# controller_rev4_1.net
KiCad netlist of a schematic drawn in EAGLE
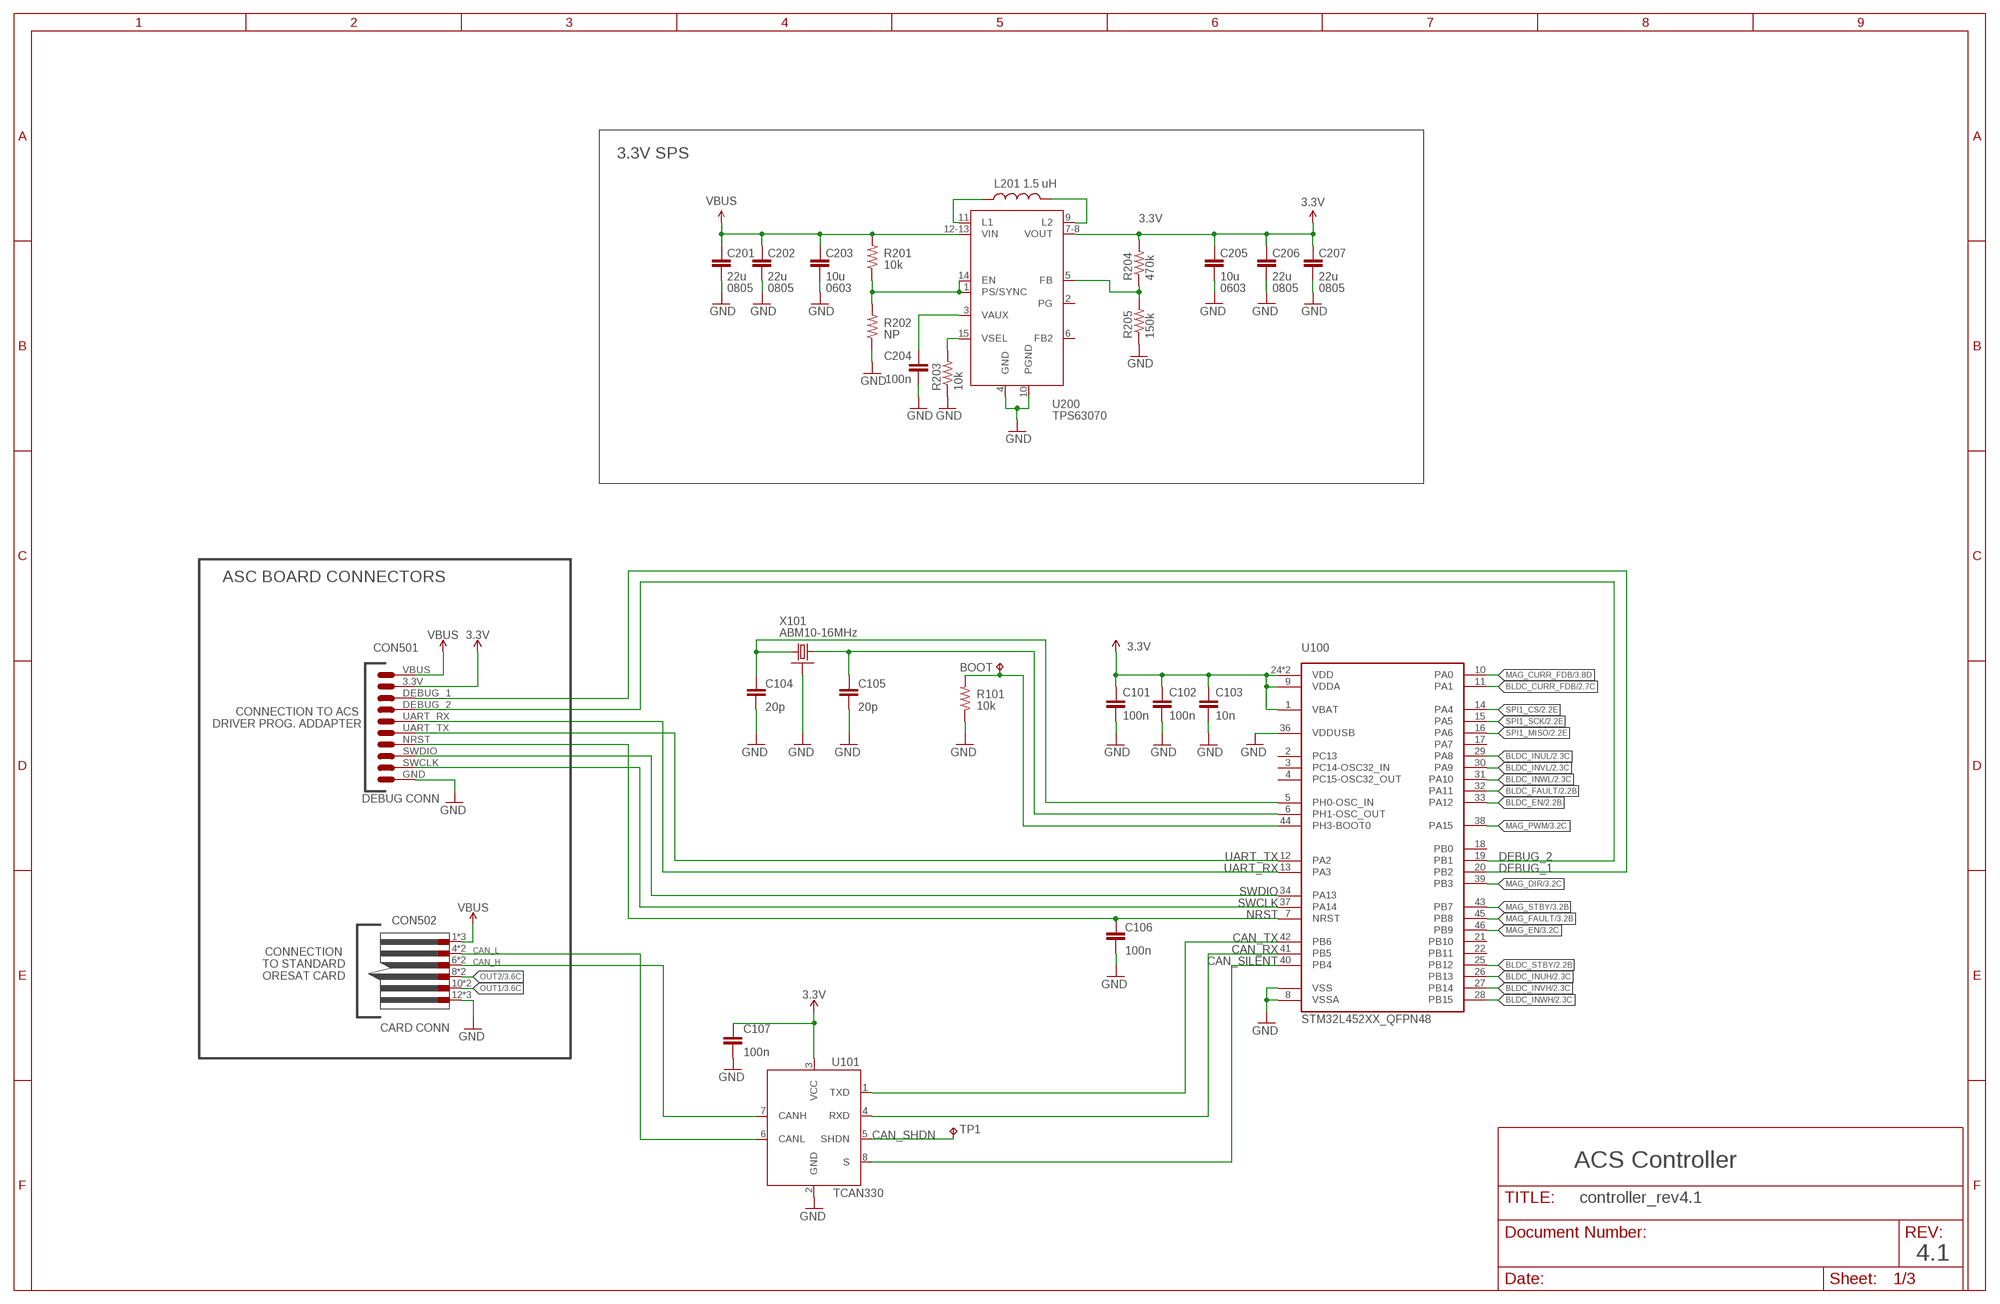
[diagram p0: schematic, sheet 1]
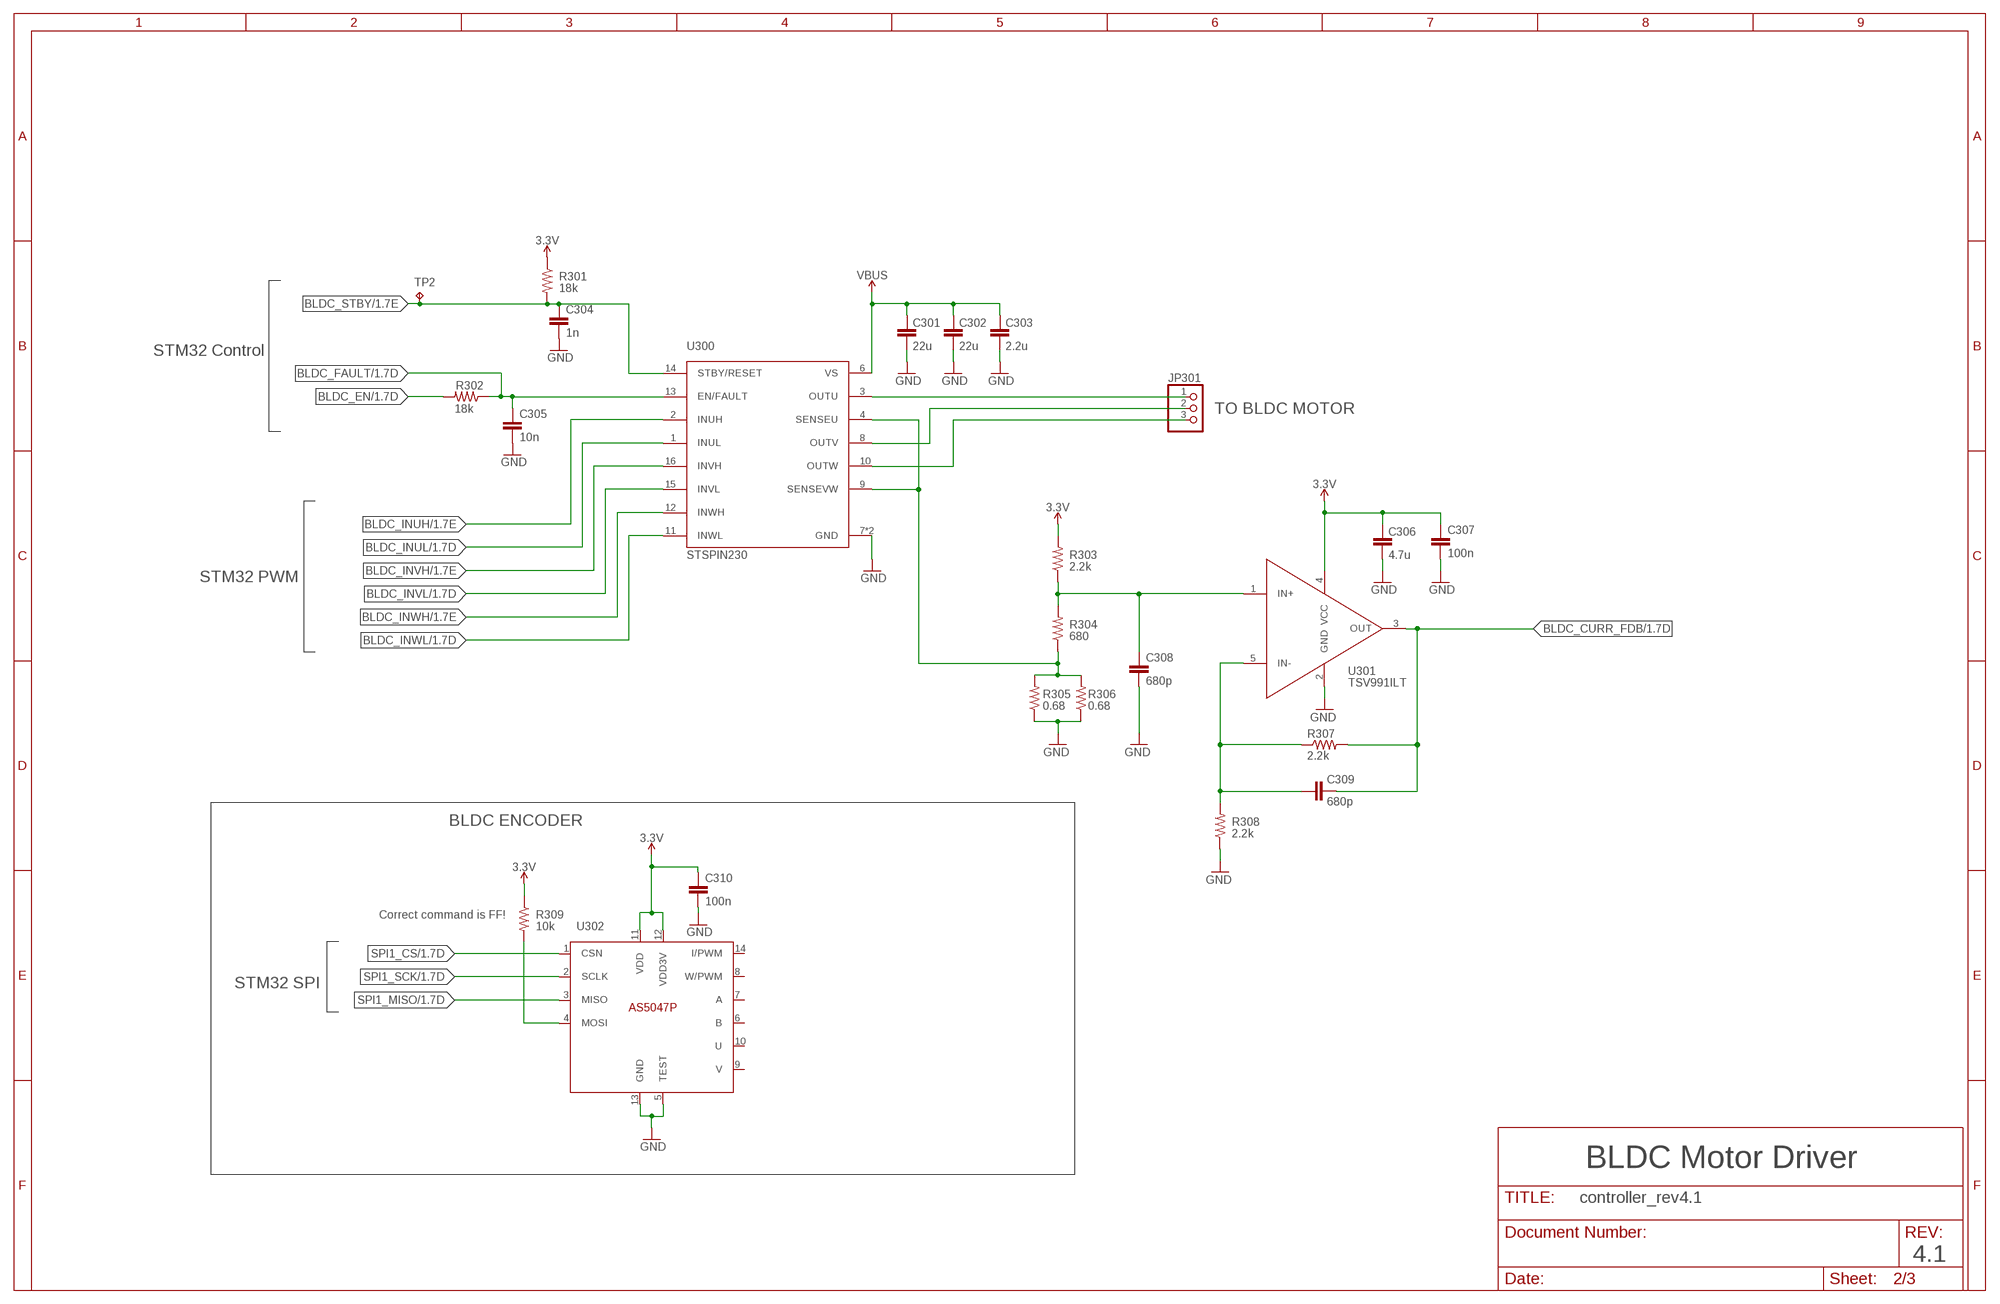
[diagram p1: schematic, sheet 2]
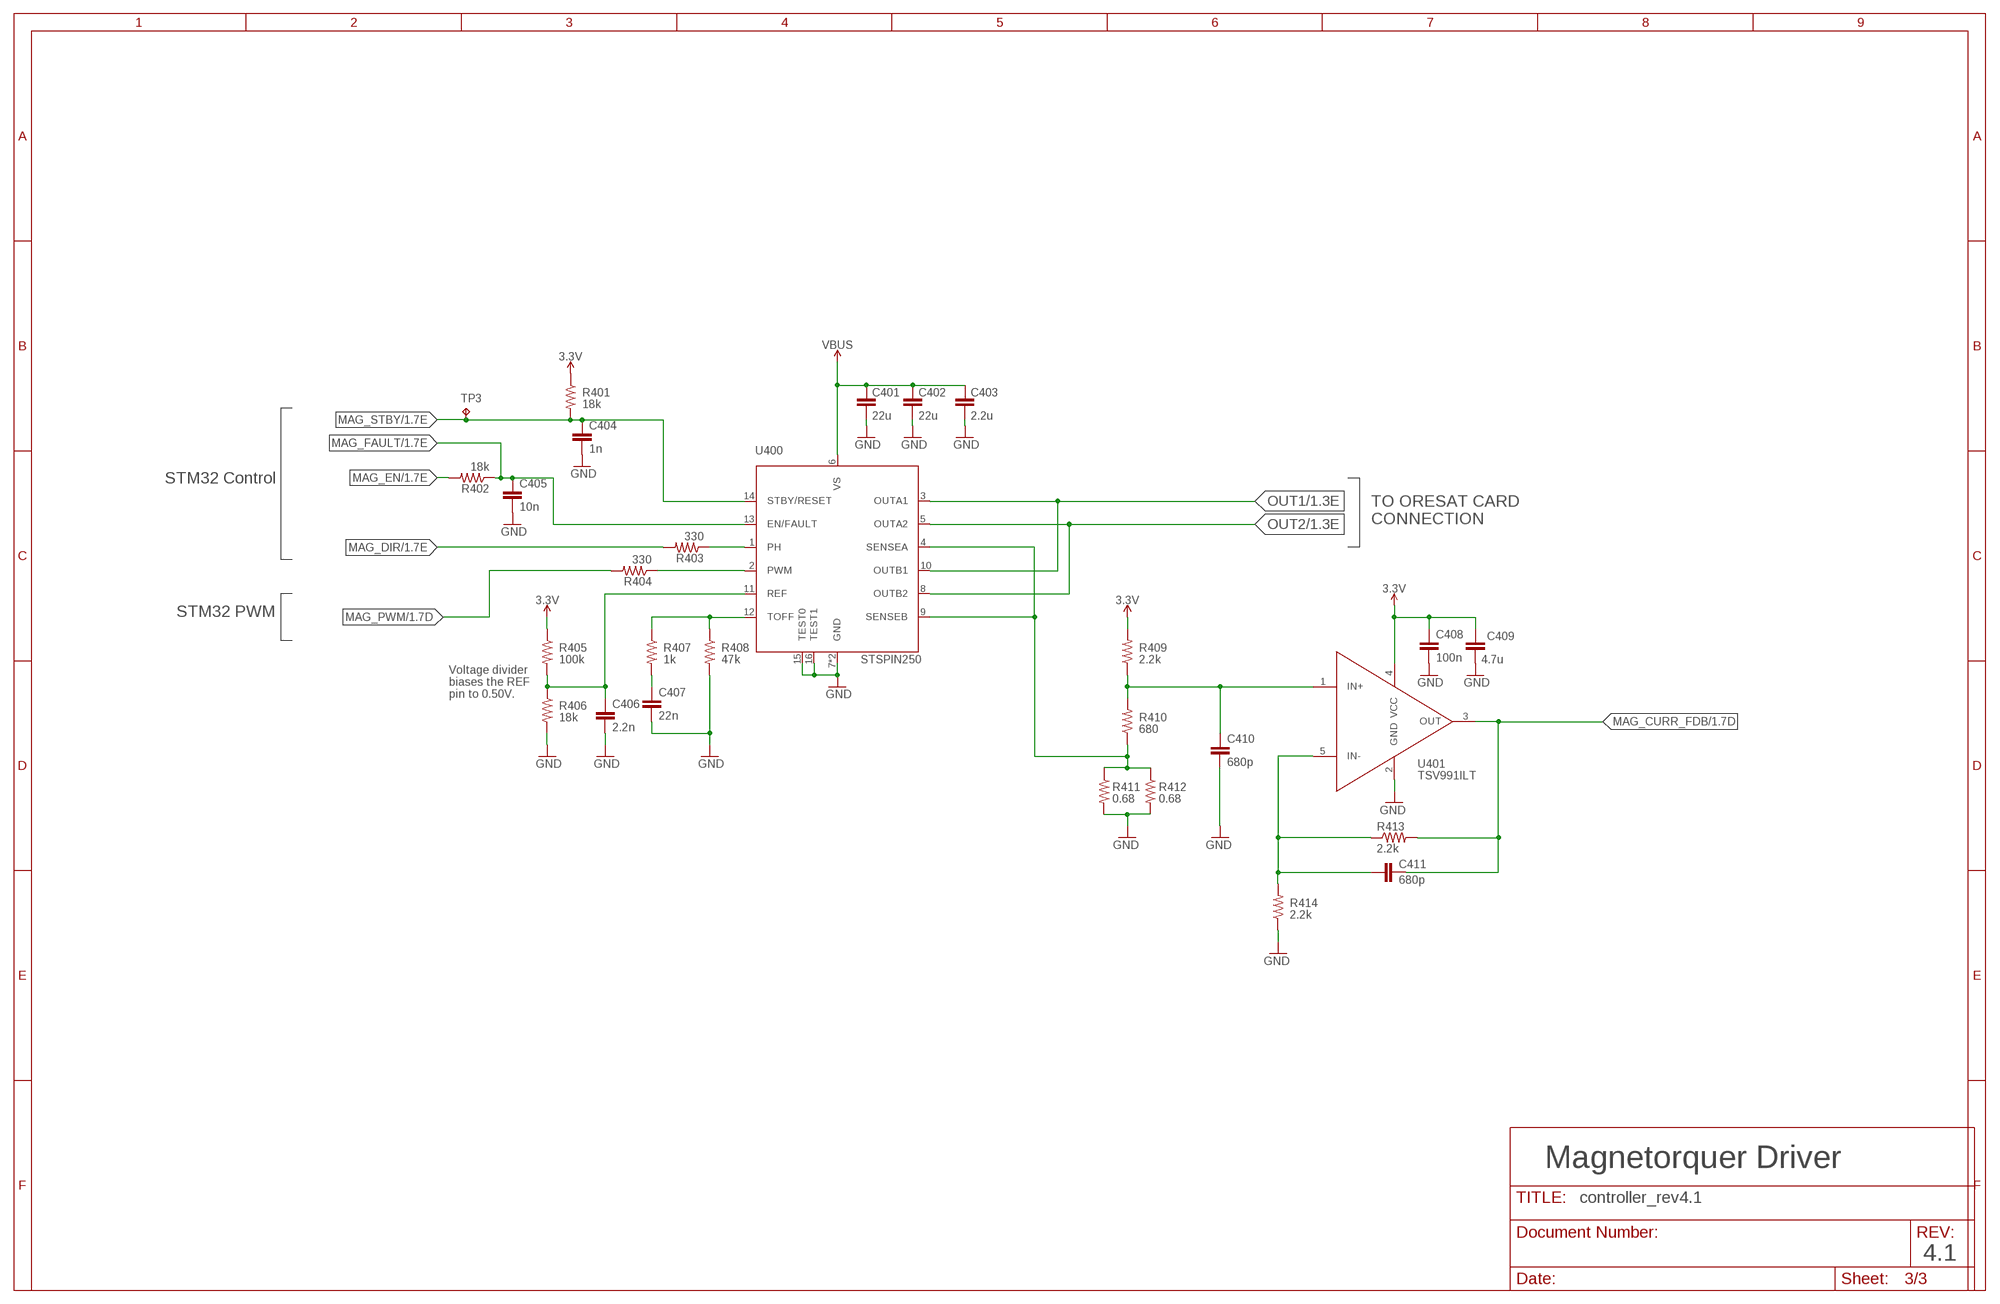
[diagram p2: schematic, sheet 3]

(export (version "E")
  (design (tool "Eeschema 10.0.6"))
  (components
    (comp (ref "BOOT")
      (value "TPTP15SQ")
      (footprint "eagle-import:TP15SQ")
      (libsource (lib "eagle-import") (part "TPTP15SQ"))
    )
    (comp (ref "C101")
      (value "100n")
      (footprint "eagle-import:.0402-B-NOSILK")
      (fields (field (name "MFR") "Samsung") (field (name "MPN") "CL05B104KO5NNNC"))
      (libsource (lib "eagle-import") (part "rcl_custom_C-EU0402-B-NOSILK"))
    )
    (comp (ref "C102")
      (value "100n")
      (footprint "eagle-import:.0402-B-NOSILK")
      (fields (field (name "MFR") "Samsung") (field (name "MPN") "CL05B104KO5NNNC"))
      (libsource (lib "eagle-import") (part "rcl_custom_C-EU0402-B-NOSILK"))
    )
    (comp (ref "C103")
      (value "10n")
      (footprint "eagle-import:.0402-B-NOSILK")
      (fields (field (name "MFR") "Samsung") (field (name "MPN") "CL05B104KO5NNNC"))
      (libsource (lib "eagle-import") (part "rcl_custom_C-EU0402-B-NOSILK"))
    )
    (comp (ref "C104")
      (value "20p")
      (footprint "eagle-import:.0402-B-NOSILK")
      (fields (field (name "MFR") "Samsung") (field (name "MPN") "CL05C200JB51PNC"))
      (libsource (lib "eagle-import") (part "rcl_custom_C-EU0402-B-NOSILK"))
    )
    (comp (ref "C105")
      (value "20p")
      (footprint "eagle-import:.0402-B-NOSILK")
      (fields (field (name "MFR") "Samsung") (field (name "MPN") "CL05C200JB51PNC"))
      (libsource (lib "eagle-import") (part "rcl_custom_C-EU0402-B-NOSILK"))
    )
    (comp (ref "C106")
      (value "100n")
      (footprint "eagle-import:.0402-B-NOSILK")
      (fields (field (name "MFR") "Samsung") (field (name "MPN") "CL05C200JB51PNC"))
      (libsource (lib "eagle-import") (part "rcl_custom_C-EU0402-B-NOSILK"))
    )
    (comp (ref "C107")
      (value "100n")
      (footprint "eagle-import:.0402-B-NOSILK")
      (fields (field (name "MFR") "Samsung") (field (name "MPN") "CL05B104KO5NNNC"))
      (libsource (lib "eagle-import") (part "rcl_custom_C-EU0402-B-NOSILK"))
    )
    (comp (ref "C201")
      (value "22u")
      (footprint "eagle-import:.0805-B-NOSILK")
      (libsource (lib "eagle-import") (part "C-EU0805-B-NOSILK"))
    )
    (comp (ref "C202")
      (value "22u")
      (footprint "eagle-import:.0805-B-NOSILK")
      (libsource (lib "eagle-import") (part "C-EU0805-B-NOSILK"))
    )
    (comp (ref "C203")
      (value "10u")
      (footprint "eagle-import:.0603-B-NOSILK")
      (fields (field (name "MFR") "Samsung") (field (name "MPN") "CL05B104KO5NNNC"))
      (libsource (lib "eagle-import") (part "C-EU0603-B-NOSILK"))
    )
    (comp (ref "C204")
      (value "100n")
      (footprint "eagle-import:.0402-B-NOSILK")
      (fields (field (name "MFR") "Samsung") (field (name "MPN") "CL05B104KO5NNNC"))
      (libsource (lib "eagle-import") (part "rcl_custom_C-EU0402-B-NOSILK"))
    )
    (comp (ref "C205")
      (value "10u")
      (footprint "eagle-import:.0603-B-NOSILK")
      (fields (field (name "MFR") "Samsung") (field (name "MPN") "CL05B104KO5NNNC"))
      (libsource (lib "eagle-import") (part "C-EU0603-B-NOSILK"))
    )
    (comp (ref "C206")
      (value "22u")
      (footprint "eagle-import:.0805-B-NOSILK")
      (libsource (lib "eagle-import") (part "C-EU0805-B-NOSILK"))
    )
    (comp (ref "C207")
      (value "22u")
      (footprint "eagle-import:.0805-B-NOSILK")
      (libsource (lib "eagle-import") (part "C-EU0805-B-NOSILK"))
    )
    (comp (ref "C501")
      (value "DEBUG_CON")
      (footprint "eagle-import:DEBUG_CON")
      (libsource (lib "eagle-import") (part "DEBUG_CON"))
    )
    (comp (ref "CON502")
      (value "CARD CONN")
      (footprint "eagle-import:LOW-PROFILE_CONNECTOR(TAB)")
      (libsource (lib "eagle-import") (part "LOW-PROFILE_CONNECTOR(TAB)"))
    )
    (comp (ref "L201")
      (value "1.5 uH")
      (footprint "eagle-import:L-COILCRAFT-XFL4020")
      (fields (field (name "MFR") "Coilcraft") (field (name "MPN") "XFL4020-152ME"))
      (libsource (lib "eagle-import") (part "L-COILCRAFT-XFL4020"))
    )
    (comp (ref "R101")
      (value "10k")
      (footprint "eagle-import:.0402-B-NOSILK")
      (fields (field (name "MFR") "Samsung") (field (name "MPN") "RC1005F6653CS"))
      (libsource (lib "eagle-import") (part "rcl_custom_R-US_0402-B-NOSILK"))
    )
    (comp (ref "R201")
      (value "10k")
      (footprint "eagle-import:.0402-B-NOSILK")
      (fields (field (name "MFR") "Samsung") (field (name "MPN") "RC1005F6653CS"))
      (libsource (lib "eagle-import") (part "rcl_custom_R-US_0402-B-NOSILK"))
    )
    (comp (ref "R202")
      (value "NP")
      (footprint "eagle-import:.0402-B-NOSILK")
      (fields (field (name "MFR") "Samsung") (field (name "MPN") "RC1005F6653CS"))
      (libsource (lib "eagle-import") (part "rcl_custom_R-US_0402-B-NOSILK"))
    )
    (comp (ref "R203")
      (value "10k")
      (footprint "eagle-import:.0402-B-NOSILK")
      (fields (field (name "MFR") "Samsung") (field (name "MPN") "RC1005F6653CS"))
      (libsource (lib "eagle-import") (part "rcl_custom_R-US_0402-B-NOSILK"))
    )
    (comp (ref "R204")
      (value "470k")
      (footprint "eagle-import:.0402-B-NOSILK")
      (fields (field (name "MFR") "Samsung") (field (name "MPN") "RC1005F6653CS"))
      (libsource (lib "eagle-import") (part "rcl_custom_R-US_0402-B-NOSILK"))
    )
    (comp (ref "R205")
      (value "150k")
      (footprint "eagle-import:.0402-B-NOSILK")
      (fields (field (name "MFR") "Samsung") (field (name "MPN") "RC1005F6653CS"))
      (libsource (lib "eagle-import") (part "rcl_custom_R-US_0402-B-NOSILK"))
    )
    (comp (ref "TP1")
      (value "TPTP06R")
      (footprint "eagle-import:TP06R")
      (libsource (lib "eagle-import") (part "TPTP06R"))
    )
    (comp (ref "U100")
      (value "STM32L452XX_QFPN48")
      (footprint "eagle-import:QFPN-48")
      (libsource (lib "eagle-import") (part "STM32L452XX_QFPN48"))
    )
    (comp (ref "U101")
      (value "TCAN330")
      (footprint "eagle-import:SOT23-8_TI-DCN")
      (fields (field (name "MFR") "Texas Instruments") (field (name "MPN") "TCAN330GDCNT"))
      (libsource (lib "eagle-import") (part "TCAN330"))
    )
    (comp (ref "U200")
      (value "TPS63070")
      (footprint "eagle-import:TPS63070X")
      (fields (field (name "MFR") "TI"))
      (libsource (lib "eagle-import") (part "TPS63070X"))
    )
    (comp (ref "X101")
      (value "ABM10-16MHz")
      (footprint "eagle-import:CRYSTAL_2.5X2")
      (fields (field (name "MFR") "ECS Inc.") (field (name "MPN") "ECS-160-10-36Q-ES-TR"))
      (libsource (lib "eagle-import") (part "CRYSTAL-WITH-GND"))
    )
    (comp (ref "C301")
      (value "22u")
      (footprint "eagle-import:.0603-B-NOSILK")
      (fields (field (name "MFR") "Samsung") (field (name "MPN") "CL05B104KO5NNNC"))
      (libsource (lib "eagle-import") (part "C-EU0603-B-NOSILK"))
    )
    (comp (ref "C302")
      (value "22u")
      (footprint "eagle-import:.0603-B-NOSILK")
      (fields (field (name "MFR") "Samsung") (field (name "MPN") "CL05B104KO5NNNC"))
      (libsource (lib "eagle-import") (part "C-EU0603-B-NOSILK"))
    )
    (comp (ref "C303")
      (value "2.2u")
      (footprint "eagle-import:.0603-B-NOSILK")
      (fields (field (name "MFR") "Samsung") (field (name "MPN") "CL05B104KO5NNNC"))
      (libsource (lib "eagle-import") (part "C-EU0603-B-NOSILK"))
    )
    (comp (ref "C304")
      (value "1n")
      (footprint "eagle-import:.0402-B-NOSILK")
      (fields (field (name "MFR") "Samsung") (field (name "MPN") "CL05B104KO5NNNC"))
      (libsource (lib "eagle-import") (part "rcl_custom_C-EU0402-B-NOSILK"))
    )
    (comp (ref "C305")
      (value "10n")
      (footprint "eagle-import:.0402-B-NOSILK")
      (fields (field (name "MFR") "Samsung") (field (name "MPN") "CL05B104KO5NNNC"))
      (libsource (lib "eagle-import") (part "rcl_custom_C-EU0402-B-NOSILK"))
    )
    (comp (ref "C306")
      (value "4.7u")
      (footprint "eagle-import:.0603-B-NOSILK")
      (fields (field (name "MFR") "Samsung") (field (name "MPN") "CL05B104KO5NNNC"))
      (libsource (lib "eagle-import") (part "C-EU0603-B-NOSILK"))
    )
    (comp (ref "C307")
      (value "100n")
      (footprint "eagle-import:.0402-B-NOSILK")
      (fields (field (name "MFR") "Samsung") (field (name "MPN") "CL05B104KO5NNNC"))
      (libsource (lib "eagle-import") (part "rcl_custom_C-EU0402-B-NOSILK"))
    )
    (comp (ref "C308")
      (value "680p")
      (footprint "eagle-import:.0402-B-NOSILK")
      (fields (field (name "MFR") "Samsung") (field (name "MPN") "CL05B104KO5NNNC"))
      (libsource (lib "eagle-import") (part "rcl_custom_C-EU0402-B-NOSILK"))
    )
    (comp (ref "C309")
      (value "680p")
      (footprint "eagle-import:.0402-B-NOSILK")
      (fields (field (name "MFR") "Samsung") (field (name "MPN") "CL05B104KO5NNNC"))
      (libsource (lib "eagle-import") (part "rcl_custom_C-EU0402-B-NOSILK"))
    )
    (comp (ref "C310")
      (value "100n")
      (footprint "eagle-import:.0402-B-NOSILK")
      (fields (field (name "MFR") "Samsung") (field (name "MPN") "CL05B104KO5NNNC"))
      (libsource (lib "eagle-import") (part "rcl_custom_C-EU0402-B-NOSILK"))
    )
    (comp (ref "JP301")
      (value "PINHD-1X03_2.00")
      (footprint "eagle-import:1X03M")
      (libsource (lib "eagle-import") (part "PINHD-1X03_2.00"))
    )
    (comp (ref "R301")
      (value "18k")
      (footprint "eagle-import:.0402-B-NOSILK")
      (fields (field (name "MFR") "Samsung") (field (name "MPN") "RC1005F6653CS"))
      (libsource (lib "eagle-import") (part "rcl_custom_R-US_0402-B-NOSILK"))
    )
    (comp (ref "R302")
      (value "18k")
      (footprint "eagle-import:.0402-B-NOSILK")
      (fields (field (name "MFR") "Samsung") (field (name "MPN") "RC1005F6653CS"))
      (libsource (lib "eagle-import") (part "rcl_custom_R-US_0402-B-NOSILK"))
    )
    (comp (ref "R303")
      (value "2.2k")
      (footprint "eagle-import:.0402-B-NOSILK")
      (fields (field (name "MFR") "Samsung") (field (name "MPN") "RC1005F6653CS"))
      (libsource (lib "eagle-import") (part "rcl_custom_R-US_0402-B-NOSILK"))
    )
    (comp (ref "R304")
      (value "680")
      (footprint "eagle-import:.0402-B-NOSILK")
      (fields (field (name "MFR") "Samsung") (field (name "MPN") "RC1005F6653CS"))
      (libsource (lib "eagle-import") (part "rcl_custom_R-US_0402-B-NOSILK"))
    )
    (comp (ref "R305")
      (value "0.68")
      (footprint "eagle-import:.0805-B-NOSILK")
      (libsource (lib "eagle-import") (part "R-US_0805-B-NOSILK"))
    )
    (comp (ref "R306")
      (value "0.68")
      (footprint "eagle-import:.0805-B-NOSILK")
      (libsource (lib "eagle-import") (part "R-US_0805-B-NOSILK"))
    )
    (comp (ref "R307")
      (value "2.2k")
      (footprint "eagle-import:.0402-B-NOSILK")
      (fields (field (name "MFR") "Samsung") (field (name "MPN") "RC1005F6653CS"))
      (libsource (lib "eagle-import") (part "rcl_custom_R-US_0402-B-NOSILK"))
    )
    (comp (ref "R308")
      (value "2.2k")
      (footprint "eagle-import:.0402-B-NOSILK")
      (fields (field (name "MFR") "Samsung") (field (name "MPN") "RC1005F6653CS"))
      (libsource (lib "eagle-import") (part "rcl_custom_R-US_0402-B-NOSILK"))
    )
    (comp (ref "R309")
      (value "10k")
      (footprint "eagle-import:.0402-B-NOSILK")
      (fields (field (name "MFR") "Samsung") (field (name "MPN") "RC1005F6653CS"))
      (libsource (lib "eagle-import") (part "rcl_custom_R-US_0402-B-NOSILK"))
    )
    (comp (ref "TP2")
      (value "TPTP06R")
      (footprint "eagle-import:TP06R")
      (libsource (lib "eagle-import") (part "TPTP06R"))
    )
    (comp (ref "U300")
      (value "STSPIN230")
      (footprint "eagle-import:VFQPN")
      (libsource (lib "eagle-import") (part "STSPIN230"))
    )
    (comp (ref "U301")
      (value "TSV991ILT")
      (footprint "eagle-import:SOT23-5")
      (libsource (lib "eagle-import") (part "TSV991ILT"))
    )
    (comp (ref "U302")
      (value "AS5047P")
      (footprint "eagle-import:TSSOP14")
      (libsource (lib "eagle-import") (part "AS5047P"))
    )
    (comp (ref "C401")
      (value "22u")
      (footprint "eagle-import:.0603-B-NOSILK")
      (fields (field (name "MFR") "Samsung") (field (name "MPN") "CL05B104KO5NNNC"))
      (libsource (lib "eagle-import") (part "C-EU0603-B-NOSILK"))
    )
    (comp (ref "C402")
      (value "22u")
      (footprint "eagle-import:.0603-B-NOSILK")
      (fields (field (name "MFR") "Samsung") (field (name "MPN") "CL05B104KO5NNNC"))
      (libsource (lib "eagle-import") (part "C-EU0603-B-NOSILK"))
    )
    (comp (ref "C403")
      (value "2.2u")
      (footprint "eagle-import:.0603-B-NOSILK")
      (fields (field (name "MFR") "Samsung") (field (name "MPN") "CL05B104KO5NNNC"))
      (libsource (lib "eagle-import") (part "C-EU0603-B-NOSILK"))
    )
    (comp (ref "C404")
      (value "1n")
      (footprint "eagle-import:.0402-B-NOSILK")
      (fields (field (name "MFR") "Samsung") (field (name "MPN") "CL05B104KO5NNNC"))
      (libsource (lib "eagle-import") (part "rcl_custom_C-EU0402-B-NOSILK"))
    )
    (comp (ref "C405")
      (value "10n")
      (footprint "eagle-import:.0402-B-NOSILK")
      (fields (field (name "MFR") "Samsung") (field (name "MPN") "CL05B104KO5NNNC"))
      (libsource (lib "eagle-import") (part "rcl_custom_C-EU0402-B-NOSILK"))
    )
    (comp (ref "C406")
      (value "2.2n")
      (footprint "eagle-import:.0402-B-NOSILK")
      (fields (field (name "MFR") "Samsung") (field (name "MPN") "CL05B104KO5NNNC"))
      (libsource (lib "eagle-import") (part "rcl_custom_C-EU0402-B-NOSILK"))
    )
    (comp (ref "C407")
      (value "22n")
      (footprint "eagle-import:.0402-B-NOSILK")
      (fields (field (name "MFR") "Samsung") (field (name "MPN") "CL05B104KO5NNNC"))
      (libsource (lib "eagle-import") (part "rcl_custom_C-EU0402-B-NOSILK"))
    )
    (comp (ref "C408")
      (value "100n")
      (footprint "eagle-import:.0402-B-NOSILK")
      (fields (field (name "MFR") "Samsung") (field (name "MPN") "CL05B104KO5NNNC"))
      (libsource (lib "eagle-import") (part "rcl_custom_C-EU0402-B-NOSILK"))
    )
    (comp (ref "C409")
      (value "4.7u")
      (footprint "eagle-import:.0603-B-NOSILK")
      (fields (field (name "MFR") "Samsung") (field (name "MPN") "CL05B104KO5NNNC"))
      (libsource (lib "eagle-import") (part "C-EU0603-B-NOSILK"))
    )
    (comp (ref "C410")
      (value "680p")
      (footprint "eagle-import:.0402-B-NOSILK")
      (fields (field (name "MFR") "Samsung") (field (name "MPN") "CL05B104KO5NNNC"))
      (libsource (lib "eagle-import") (part "rcl_custom_C-EU0402-B-NOSILK"))
    )
    (comp (ref "C411")
      (value "680p")
      (footprint "eagle-import:.0402-B-NOSILK")
      (fields (field (name "MFR") "Samsung") (field (name "MPN") "CL05B104KO5NNNC"))
      (libsource (lib "eagle-import") (part "rcl_custom_C-EU0402-B-NOSILK"))
    )
    (comp (ref "R401")
      (value "18k")
      (footprint "eagle-import:.0402-B-NOSILK")
      (fields (field (name "MFR") "Samsung") (field (name "MPN") "RC1005F6653CS"))
      (libsource (lib "eagle-import") (part "rcl_custom_R-US_0402-B-NOSILK"))
    )
    (comp (ref "R402")
      (value "18k")
      (footprint "eagle-import:.0402-B-NOSILK")
      (fields (field (name "MFR") "Samsung") (field (name "MPN") "RC1005F6653CS"))
      (libsource (lib "eagle-import") (part "rcl_custom_R-US_0402-B-NOSILK"))
    )
    (comp (ref "R403")
      (value "330")
      (footprint "eagle-import:.0402-B-NOSILK")
      (fields (field (name "MFR") "Samsung") (field (name "MPN") "RC1005F6653CS"))
      (libsource (lib "eagle-import") (part "rcl_custom_R-US_0402-B-NOSILK"))
    )
    (comp (ref "R404")
      (value "330")
      (footprint "eagle-import:.0402-B-NOSILK")
      (fields (field (name "MFR") "Samsung") (field (name "MPN") "RC1005F6653CS"))
      (libsource (lib "eagle-import") (part "rcl_custom_R-US_0402-B-NOSILK"))
    )
    (comp (ref "R405")
      (value "100k")
      (footprint "eagle-import:.0402-B-NOSILK")
      (fields (field (name "MFR") "Samsung") (field (name "MPN") "RC1005F6653CS"))
      (libsource (lib "eagle-import") (part "rcl_custom_R-US_0402-B-NOSILK"))
    )
    (comp (ref "R406")
      (value "18k")
      (footprint "eagle-import:.0402-B-NOSILK")
      (fields (field (name "MFR") "Samsung") (field (name "MPN") "RC1005F6653CS"))
      (libsource (lib "eagle-import") (part "rcl_custom_R-US_0402-B-NOSILK"))
    )
    (comp (ref "R407")
      (value "1k")
      (footprint "eagle-import:.0402-B-NOSILK")
      (fields (field (name "MFR") "Samsung") (field (name "MPN") "RC1005F6653CS"))
      (libsource (lib "eagle-import") (part "rcl_custom_R-US_0402-B-NOSILK"))
    )
    (comp (ref "R408")
      (value "47k")
      (footprint "eagle-import:.0402-B-NOSILK")
      (fields (field (name "MFR") "Samsung") (field (name "MPN") "RC1005F6653CS"))
      (libsource (lib "eagle-import") (part "rcl_custom_R-US_0402-B-NOSILK"))
    )
    (comp (ref "R409")
      (value "2.2k")
      (footprint "eagle-import:.0402-B-NOSILK")
      (fields (field (name "MFR") "Samsung") (field (name "MPN") "RC1005F6653CS"))
      (libsource (lib "eagle-import") (part "rcl_custom_R-US_0402-B-NOSILK"))
    )
    (comp (ref "R410")
      (value "680")
      (footprint "eagle-import:.0402-B-NOSILK")
      (fields (field (name "MFR") "Samsung") (field (name "MPN") "RC1005F6653CS"))
      (libsource (lib "eagle-import") (part "rcl_custom_R-US_0402-B-NOSILK"))
    )
    (comp (ref "R411")
      (value "0.68")
      (footprint "eagle-import:.0805-B-NOSILK")
      (libsource (lib "eagle-import") (part "R-US_0805-B-NOSILK"))
    )
    (comp (ref "R412")
      (value "0.68")
      (footprint "eagle-import:.0805-B-NOSILK")
      (libsource (lib "eagle-import") (part "R-US_0805-B-NOSILK"))
    )
    (comp (ref "R413")
      (value "2.2k")
      (footprint "eagle-import:.0402-B-NOSILK")
      (fields (field (name "MFR") "Samsung") (field (name "MPN") "RC1005F6653CS"))
      (libsource (lib "eagle-import") (part "rcl_custom_R-US_0402-B-NOSILK"))
    )
    (comp (ref "R414")
      (value "2.2k")
      (footprint "eagle-import:.0402-B-NOSILK")
      (fields (field (name "MFR") "Samsung") (field (name "MPN") "RC1005F6653CS"))
      (libsource (lib "eagle-import") (part "rcl_custom_R-US_0402-B-NOSILK"))
    )
    (comp (ref "TP3")
      (value "TPTP06R")
      (footprint "eagle-import:TP06R")
      (libsource (lib "eagle-import") (part "TPTP06R"))
    )
    (comp (ref "U400")
      (value "STSPIN250")
      (footprint "eagle-import:VFQPN")
      (libsource (lib "eagle-import") (part "STSPIN250"))
    )
    (comp (ref "U401")
      (value "TSV991ILT")
      (footprint "eagle-import:SOT23-5")
      (libsource (lib "eagle-import") (part "TSV991ILT"))
    )
  )
  (nets
    (net (code "1") (name "3.3V") (class "Default")
      (node (ref "C101") (pin "1") (pinfunction "1_1") (pintype "passive"))
      (node (ref "C102") (pin "1") (pinfunction "1_1") (pintype "passive"))
      (node (ref "C103") (pin "1") (pinfunction "1_1") (pintype "passive"))
      (node (ref "C107") (pin "1") (pinfunction "1_1") (pintype "passive"))
      (node (ref "C205") (pin "1") (pinfunction "1_1") (pintype "passive"))
      (node (ref "C206") (pin "1") (pinfunction "1_1") (pintype "passive"))
      (node (ref "C207") (pin "1") (pinfunction "1_1") (pintype "passive"))
      (node (ref "C306") (pin "1") (pinfunction "1_1") (pintype "passive"))
      (node (ref "C307") (pin "1") (pinfunction "1_1") (pintype "passive"))
      (node (ref "C310") (pin "1") (pinfunction "1_1") (pintype "passive"))
      (node (ref "C408") (pin "1") (pinfunction "1_1") (pintype "passive"))
      (node (ref "C409") (pin "1") (pinfunction "1_1") (pintype "passive"))
      (node (ref "C501") (pin "3.3V") (pinfunction "2_3.3V") (pintype "bidirectional"))
      (node (ref "R204") (pin "2") (pinfunction "2_2") (pintype "passive"))
      (node (ref "R301") (pin "1") (pinfunction "1_1") (pintype "passive"))
      (node (ref "R303") (pin "2") (pinfunction "2_2") (pintype "passive"))
      (node (ref "R309") (pin "1") (pinfunction "1_1") (pintype "passive"))
      (node (ref "R401") (pin "1") (pinfunction "1_1") (pintype "passive"))
      (node (ref "R405") (pin "1") (pinfunction "1_1") (pintype "passive"))
      (node (ref "R409") (pin "2") (pinfunction "2_2") (pintype "passive"))
      (node (ref "U100") (pin "1") (pinfunction "VBAT_1") (pintype "bidirectional"))
      (node (ref "U100") (pin "24") (pinfunction "VDD_24") (pintype "bidirectional"))
      (node (ref "U100") (pin "48") (pinfunction "VDD_48") (pintype "bidirectional"))
      (node (ref "U100") (pin "9") (pinfunction "VDDA_9") (pintype "bidirectional"))
      (node (ref "U101") (pin "3") (pinfunction "VCC_3") (pintype "power_in"))
      (node (ref "U200") (pin "7-8") (pinfunction "VOUT_7-8") (pintype "power_in"))
      (node (ref "U301") (pin "4") (pinfunction "VCC_4") (pintype "bidirectional"))
      (node (ref "U302") (pin "11") (pinfunction "VDD_11") (pintype "power_in"))
      (node (ref "U302") (pin "12") (pinfunction "VDD3V_12") (pintype "power_in"))
      (node (ref "U401") (pin "4") (pinfunction "VCC_4") (pintype "bidirectional"))
    )
    (net (code "2") (name "BLDC_CURR_FDB") (class "Default")
      (node (ref "C309") (pin "1") (pinfunction "1_1") (pintype "passive"))
      (node (ref "R307") (pin "2") (pinfunction "2_2") (pintype "passive"))
      (node (ref "U100") (pin "11") (pinfunction "PA1_11") (pintype "bidirectional"))
      (node (ref "U301") (pin "3") (pinfunction "OUT_3") (pintype "bidirectional"))
    )
    (net (code "3") (name "BLDC_EN") (class "Default")
      (node (ref "R302") (pin "2") (pinfunction "2_2") (pintype "passive"))
      (node (ref "U100") (pin "33") (pinfunction "PA12_33") (pintype "bidirectional"))
    )
    (net (code "4") (name "BLDC_FAULT") (class "Default")
      (node (ref "C305") (pin "1") (pinfunction "1_1") (pintype "passive"))
      (node (ref "R302") (pin "1") (pinfunction "1_1") (pintype "passive"))
      (node (ref "U100") (pin "32") (pinfunction "PA11_32") (pintype "bidirectional"))
      (node (ref "U300") (pin "13") (pinfunction "EN/FAULT_13") (pintype "bidirectional"))
    )
    (net (code "5") (name "BLDC_INUH") (class "Default")
      (node (ref "U100") (pin "26") (pinfunction "PB13_26") (pintype "bidirectional"))
      (node (ref "U300") (pin "2") (pinfunction "INUH_2") (pintype "input"))
    )
    (net (code "6") (name "BLDC_INUL") (class "Default")
      (node (ref "U100") (pin "29") (pinfunction "PA8_29") (pintype "bidirectional"))
      (node (ref "U300") (pin "1") (pinfunction "INUL_1") (pintype "input"))
    )
    (net (code "7") (name "BLDC_INVH") (class "Default")
      (node (ref "U100") (pin "27") (pinfunction "PB14_27") (pintype "bidirectional"))
      (node (ref "U300") (pin "16") (pinfunction "INVH_16") (pintype "input"))
    )
    (net (code "8") (name "BLDC_INVL") (class "Default")
      (node (ref "U100") (pin "30") (pinfunction "PA9_30") (pintype "bidirectional"))
      (node (ref "U300") (pin "15") (pinfunction "INVL_15") (pintype "input"))
    )
    (net (code "9") (name "BLDC_INWH") (class "Default")
      (node (ref "U100") (pin "28") (pinfunction "PB15_28") (pintype "bidirectional"))
      (node (ref "U300") (pin "12") (pinfunction "INWH_12") (pintype "input"))
    )
    (net (code "10") (name "BLDC_INWL") (class "Default")
      (node (ref "U100") (pin "31") (pinfunction "PA10_31") (pintype "bidirectional"))
      (node (ref "U300") (pin "11") (pinfunction "INWL_11") (pintype "input"))
    )
    (net (code "11") (name "BLDC_STBY") (class "Default")
      (node (ref "C304") (pin "1") (pinfunction "1_1") (pintype "passive"))
      (node (ref "R301") (pin "2") (pinfunction "2_2") (pintype "passive"))
      (node (ref "TP2") (pin "TP") (pinfunction "TP_TP") (pintype "input"))
      (node (ref "U100") (pin "25") (pinfunction "PB12_25") (pintype "bidirectional"))
      (node (ref "U300") (pin "14") (pinfunction "STBY/RESET_14") (pintype "input"))
    )
    (net (code "12") (name "CAN_H") (class "Default")
      (node (ref "CON502") (pin "6") (pinfunction "3_6") (pintype "bidirectional"))
      (node (ref "CON502") (pin "7") (pinfunction "3_7") (pintype "bidirectional"))
      (node (ref "U101") (pin "7") (pinfunction "CANH_7") (pintype "bidirectional"))
    )
    (net (code "13") (name "CAN_L") (class "Default")
      (node (ref "CON502") (pin "4") (pinfunction "2_4") (pintype "bidirectional"))
      (node (ref "CON502") (pin "5") (pinfunction "2_5") (pintype "bidirectional"))
      (node (ref "U101") (pin "6") (pinfunction "CANL_6") (pintype "bidirectional"))
    )
    (net (code "14") (name "CAN_RX") (class "Default")
      (node (ref "U100") (pin "41") (pinfunction "PB5_41") (pintype "bidirectional"))
      (node (ref "U101") (pin "4") (pinfunction "RXD_4") (pintype "output"))
    )
    (net (code "15") (name "CAN_SHDN") (class "Default")
      (node (ref "TP1") (pin "TP") (pinfunction "TP_TP") (pintype "input"))
      (node (ref "U101") (pin "5") (pinfunction "SHDN_5") (pintype "input"))
    )
    (net (code "16") (name "CAN_SILENT") (class "Default")
      (node (ref "U100") (pin "40") (pinfunction "PB4_40") (pintype "bidirectional"))
      (node (ref "U101") (pin "8") (pinfunction "S_8") (pintype "input"))
    )
    (net (code "17") (name "CAN_TX") (class "Default")
      (node (ref "U100") (pin "42") (pinfunction "PB6_42") (pintype "bidirectional"))
      (node (ref "U101") (pin "1") (pinfunction "TXD_1") (pintype "input"))
    )
    (net (code "18") (name "DEBUG_1") (class "Default")
      (node (ref "C501") (pin "DEBUG_1") (pinfunction "3_DEBUG_1") (pintype "bidirectional"))
      (node (ref "U100") (pin "20") (pinfunction "PB2_20") (pintype "bidirectional"))
    )
    (net (code "19") (name "DEBUG_2") (class "Default")
      (node (ref "C501") (pin "DEBUG_2") (pinfunction "4_DEBUG_2") (pintype "bidirectional"))
      (node (ref "U100") (pin "19") (pinfunction "PB1_19") (pintype "bidirectional"))
    )
    (net (code "20") (name "GND") (class "Default")
      (node (ref "C101") (pin "2") (pinfunction "2_2") (pintype "passive"))
      (node (ref "C102") (pin "2") (pinfunction "2_2") (pintype "passive"))
      (node (ref "C103") (pin "2") (pinfunction "2_2") (pintype "passive"))
      (node (ref "C104") (pin "2") (pinfunction "2_2") (pintype "passive"))
      (node (ref "C105") (pin "2") (pinfunction "2_2") (pintype "passive"))
      (node (ref "C106") (pin "2") (pinfunction "2_2") (pintype "passive"))
      (node (ref "C107") (pin "2") (pinfunction "2_2") (pintype "passive"))
      (node (ref "C201") (pin "2") (pinfunction "2_2") (pintype "passive"))
      (node (ref "C202") (pin "2") (pinfunction "2_2") (pintype "passive"))
      (node (ref "C203") (pin "2") (pinfunction "2_2") (pintype "passive"))
      (node (ref "C204") (pin "2") (pinfunction "2_2") (pintype "passive"))
      (node (ref "C205") (pin "2") (pinfunction "2_2") (pintype "passive"))
      (node (ref "C206") (pin "2") (pinfunction "2_2") (pintype "passive"))
      (node (ref "C207") (pin "2") (pinfunction "2_2") (pintype "passive"))
      (node (ref "C301") (pin "2") (pinfunction "2_2") (pintype "passive"))
      (node (ref "C302") (pin "2") (pinfunction "2_2") (pintype "passive"))
      (node (ref "C303") (pin "2") (pinfunction "2_2") (pintype "passive"))
      (node (ref "C304") (pin "2") (pinfunction "2_2") (pintype "passive"))
      (node (ref "C305") (pin "2") (pinfunction "2_2") (pintype "passive"))
      (node (ref "C306") (pin "2") (pinfunction "2_2") (pintype "passive"))
      (node (ref "C307") (pin "2") (pinfunction "2_2") (pintype "passive"))
      (node (ref "C308") (pin "2") (pinfunction "2_2") (pintype "passive"))
      (node (ref "C310") (pin "2") (pinfunction "2_2") (pintype "passive"))
      (node (ref "C401") (pin "2") (pinfunction "2_2") (pintype "passive"))
      (node (ref "C402") (pin "2") (pinfunction "2_2") (pintype "passive"))
      (node (ref "C403") (pin "2") (pinfunction "2_2") (pintype "passive"))
      (node (ref "C404") (pin "2") (pinfunction "2_2") (pintype "passive"))
      (node (ref "C405") (pin "2") (pinfunction "2_2") (pintype "passive"))
      (node (ref "C406") (pin "2") (pinfunction "2_2") (pintype "passive"))
      (node (ref "C407") (pin "2") (pinfunction "2_2") (pintype "passive"))
      (node (ref "C408") (pin "2") (pinfunction "2_2") (pintype "passive"))
      (node (ref "C409") (pin "2") (pinfunction "2_2") (pintype "passive"))
      (node (ref "C410") (pin "2") (pinfunction "2_2") (pintype "passive"))
      (node (ref "C501") (pin "GND") (pinfunction "10_GND") (pintype "bidirectional"))
      (node (ref "CON502") (pin "12") (pinfunction "6_12") (pintype "bidirectional"))
      (node (ref "CON502") (pin "13") (pinfunction "6_13") (pintype "bidirectional"))
      (node (ref "CON502") (pin "14") (pinfunction "6_14") (pintype "bidirectional"))
      (node (ref "R101") (pin "1") (pinfunction "1_1") (pintype "passive"))
      (node (ref "R202") (pin "1") (pinfunction "1_1") (pintype "passive"))
      (node (ref "R203") (pin "1") (pinfunction "1_1") (pintype "passive"))
      (node (ref "R205") (pin "1") (pinfunction "1_1") (pintype "passive"))
      (node (ref "R305") (pin "1") (pinfunction "1_1") (pintype "passive"))
      (node (ref "R306") (pin "1") (pinfunction "1_1") (pintype "passive"))
      (node (ref "R308") (pin "1") (pinfunction "1_1") (pintype "passive"))
      (node (ref "R406") (pin "2") (pinfunction "2_2") (pintype "passive"))
      (node (ref "R408") (pin "2") (pinfunction "2_2") (pintype "passive"))
      (node (ref "R411") (pin "2") (pinfunction "2_2") (pintype "passive"))
      (node (ref "R412") (pin "2") (pinfunction "2_2") (pintype "passive"))
      (node (ref "R414") (pin "1") (pinfunction "1_1") (pintype "passive"))
      (node (ref "U100") (pin "23") (pinfunction "VSS_23") (pintype "bidirectional"))
      (node (ref "U100") (pin "35") (pinfunction "VSS_35") (pintype "bidirectional"))
      (node (ref "U100") (pin "36") (pinfunction "VDDUSB_36") (pintype "bidirectional"))
      (node (ref "U100") (pin "47") (pinfunction "VSS_47") (pintype "bidirectional"))
      (node (ref "U100") (pin "8") (pinfunction "VSSA_8") (pintype "bidirectional"))
      (node (ref "U100") (pin "EPAD") (pinfunction "VSS_EPAD") (pintype "bidirectional"))
      (node (ref "U101") (pin "2") (pinfunction "GND_2") (pintype "power_in"))
      (node (ref "U200") (pin "10") (pinfunction "PGND_10") (pintype "power_in"))
      (node (ref "U200") (pin "4") (pinfunction "GND_4") (pintype "power_in"))
      (node (ref "U300") (pin "7") (pinfunction "GND_7") (pintype "power_in"))
      (node (ref "U300") (pin "EPAD") (pinfunction "GND_EPAD") (pintype "power_in"))
      (node (ref "U301") (pin "2") (pinfunction "GND_2") (pintype "bidirectional"))
      (node (ref "U302") (pin "13") (pinfunction "GND_13") (pintype "power_in"))
      (node (ref "U302") (pin "5") (pinfunction "TEST_5") (pintype "power_in"))
      (node (ref "U400") (pin "15") (pinfunction "TEST0_15") (pintype "bidirectional"))
      (node (ref "U400") (pin "16") (pinfunction "TEST1_16") (pintype "bidirectional"))
      (node (ref "U400") (pin "7") (pinfunction "GND_7") (pintype "power_in"))
      (node (ref "U400") (pin "EPAD") (pinfunction "GND_EPAD") (pintype "power_in"))
      (node (ref "U401") (pin "2") (pinfunction "GND_2") (pintype "bidirectional"))
      (node (ref "X101") (pin "2") (pinfunction "SHIELD_2") (pintype "power_in"))
      (node (ref "X101") (pin "4") (pinfunction "SHIELD_4") (pintype "power_in"))
    )
    (net (code "21") (name "MAG_CURR_FDB") (class "Default")
      (node (ref "C411") (pin "1") (pinfunction "1_1") (pintype "passive"))
      (node (ref "R413") (pin "2") (pinfunction "2_2") (pintype "passive"))
      (node (ref "U100") (pin "10") (pinfunction "PA0_10") (pintype "bidirectional"))
      (node (ref "U401") (pin "3") (pinfunction "OUT_3") (pintype "bidirectional"))
    )
    (net (code "22") (name "MAG_DIR") (class "Default")
      (node (ref "R403") (pin "2") (pinfunction "2_2") (pintype "passive"))
      (node (ref "U100") (pin "39") (pinfunction "PB3_39") (pintype "bidirectional"))
    )
    (net (code "23") (name "MAG_EN") (class "Default")
      (node (ref "R402") (pin "2") (pinfunction "2_2") (pintype "passive"))
      (node (ref "U100") (pin "46") (pinfunction "PB9_46") (pintype "bidirectional"))
    )
    (net (code "24") (name "MAG_FAULT") (class "Default")
      (node (ref "C405") (pin "1") (pinfunction "1_1") (pintype "passive"))
      (node (ref "R402") (pin "1") (pinfunction "1_1") (pintype "passive"))
      (node (ref "U100") (pin "45") (pinfunction "PB8_45") (pintype "bidirectional"))
      (node (ref "U400") (pin "13") (pinfunction "EN/FAULT_13") (pintype "bidirectional"))
    )
    (net (code "25") (name "MAG_PWM") (class "Default")
      (node (ref "R404") (pin "2") (pinfunction "2_2") (pintype "passive"))
      (node (ref "U100") (pin "38") (pinfunction "PA15_38") (pintype "bidirectional"))
    )
    (net (code "26") (name "MAG_STBY") (class "Default")
      (node (ref "C404") (pin "1") (pinfunction "1_1") (pintype "passive"))
      (node (ref "R401") (pin "2") (pinfunction "2_2") (pintype "passive"))
      (node (ref "TP3") (pin "TP") (pinfunction "TP_TP") (pintype "input"))
      (node (ref "U100") (pin "43") (pinfunction "PB7_43") (pintype "bidirectional"))
      (node (ref "U400") (pin "14") (pinfunction "STBY/RESET_14") (pintype "bidirectional"))
    )
    (net (code "27") (name "NRST") (class "Default")
      (node (ref "C106") (pin "1") (pinfunction "1_1") (pintype "passive"))
      (node (ref "C501") (pin "NRST") (pinfunction "7_NRST") (pintype "bidirectional"))
      (node (ref "U100") (pin "7") (pinfunction "NRST_7") (pintype "bidirectional"))
    )
    (net (code "28") (name "Net-(C407-Pad1)") (class "Default")
      (node (ref "C407") (pin "1") (pinfunction "1_1") (pintype "passive"))
      (node (ref "R407") (pin "2") (pinfunction "2_2") (pintype "passive"))
    )
    (net (code "29") (name "Net-(U100-PH0-OSC_IN)") (class "Default")
      (node (ref "C104") (pin "1") (pinfunction "1_1") (pintype "passive"))
      (node (ref "U100") (pin "5") (pinfunction "PH0-OSC_IN_5") (pintype "bidirectional"))
      (node (ref "X101") (pin "3") (pinfunction "2_3") (pintype "passive"))
    )
    (net (code "30") (name "Net-(U100-PH1-OSC_OUT)") (class "Default")
      (node (ref "C105") (pin "1") (pinfunction "1_1") (pintype "passive"))
      (node (ref "U100") (pin "6") (pinfunction "PH1-OSC_OUT_6") (pintype "bidirectional"))
      (node (ref "X101") (pin "1") (pinfunction "1_1") (pintype "passive"))
    )
    (net (code "31") (name "Net-(U100-PH3-BOOT0)") (class "Default")
      (node (ref "BOOT") (pin "TP") (pinfunction "TP_TP") (pintype "input"))
      (node (ref "R101") (pin "2") (pinfunction "2_2") (pintype "passive"))
      (node (ref "U100") (pin "44") (pinfunction "PH3-BOOT0_44") (pintype "bidirectional"))
    )
    (net (code "32") (name "Net-(U200-EN)") (class "Default")
      (node (ref "R201") (pin "1") (pinfunction "1_1") (pintype "passive"))
      (node (ref "R202") (pin "2") (pinfunction "2_2") (pintype "passive"))
      (node (ref "U200") (pin "1") (pinfunction "PS/SYNC_1") (pintype "input"))
      (node (ref "U200") (pin "14") (pinfunction "EN_14") (pintype "input"))
    )
    (net (code "33") (name "Net-(U200-FB)") (class "Default")
      (node (ref "R204") (pin "1") (pinfunction "1_1") (pintype "passive"))
      (node (ref "R205") (pin "2") (pinfunction "2_2") (pintype "passive"))
      (node (ref "U200") (pin "5") (pinfunction "FB_5") (pintype "passive"))
    )
    (net (code "34") (name "Net-(U200-L1)") (class "Default")
      (node (ref "L201") (pin "1") (pinfunction "1_1") (pintype "passive"))
      (node (ref "U200") (pin "11") (pinfunction "L1_11") (pintype "passive"))
    )
    (net (code "35") (name "Net-(U200-L2)") (class "Default")
      (node (ref "L201") (pin "2") (pinfunction "2_2") (pintype "passive"))
      (node (ref "U200") (pin "9") (pinfunction "L2_9") (pintype "passive"))
    )
    (net (code "36") (name "Net-(U200-VAUX)") (class "Default")
      (node (ref "C204") (pin "1") (pinfunction "1_1") (pintype "passive"))
      (node (ref "U200") (pin "3") (pinfunction "VAUX_3") (pintype "output"))
    )
    (net (code "37") (name "Net-(U200-VSEL)") (class "Default")
      (node (ref "R203") (pin "2") (pinfunction "2_2") (pintype "passive"))
      (node (ref "U200") (pin "15") (pinfunction "VSEL_15") (pintype "input"))
    )
    (net (code "38") (name "Net-(U300-OUTU)") (class "Default")
      (node (ref "JP301") (pin "1") (pinfunction "1_1") (pintype "passive"))
      (node (ref "U300") (pin "3") (pinfunction "OUTU_3") (pintype "output"))
    )
    (net (code "39") (name "Net-(U300-OUTV)") (class "Default")
      (node (ref "JP301") (pin "2") (pinfunction "2_2") (pintype "passive"))
      (node (ref "U300") (pin "8") (pinfunction "OUTV_8") (pintype "output"))
    )
    (net (code "40") (name "Net-(U300-OUTW)") (class "Default")
      (node (ref "JP301") (pin "3") (pinfunction "3_3") (pintype "passive"))
      (node (ref "U300") (pin "10") (pinfunction "OUTW_10") (pintype "output"))
    )
    (net (code "41") (name "Net-(U300-SENSEU)") (class "Default")
      (node (ref "R304") (pin "1") (pinfunction "1_1") (pintype "passive"))
      (node (ref "R305") (pin "2") (pinfunction "2_2") (pintype "passive"))
      (node (ref "R306") (pin "2") (pinfunction "2_2") (pintype "passive"))
      (node (ref "U300") (pin "4") (pinfunction "SENSEU_4") (pintype "output"))
      (node (ref "U300") (pin "9") (pinfunction "SENSEVW_9") (pintype "output"))
    )
    (net (code "42") (name "Net-(U301-IN+)") (class "Default")
      (node (ref "C308") (pin "1") (pinfunction "1_1") (pintype "passive"))
      (node (ref "R303") (pin "1") (pinfunction "1_1") (pintype "passive"))
      (node (ref "R304") (pin "2") (pinfunction "2_2") (pintype "passive"))
      (node (ref "U301") (pin "1") (pinfunction "IN+_1") (pintype "bidirectional"))
    )
    (net (code "43") (name "Net-(U301-IN-)") (class "Default")
      (node (ref "C309") (pin "2") (pinfunction "2_2") (pintype "passive"))
      (node (ref "R307") (pin "1") (pinfunction "1_1") (pintype "passive"))
      (node (ref "R308") (pin "2") (pinfunction "2_2") (pintype "passive"))
      (node (ref "U301") (pin "5") (pinfunction "IN-_5") (pintype "bidirectional"))
    )
    (net (code "44") (name "Net-(U302-MOSI)") (class "Default")
      (node (ref "R309") (pin "2") (pinfunction "2_2") (pintype "passive"))
      (node (ref "U302") (pin "4") (pinfunction "MOSI_4") (pintype "input"))
    )
    (net (code "45") (name "Net-(U400-PH)") (class "Default")
      (node (ref "R403") (pin "1") (pinfunction "1_1") (pintype "passive"))
      (node (ref "U400") (pin "1") (pinfunction "PH_1") (pintype "input"))
    )
    (net (code "46") (name "Net-(U400-PWM)") (class "Default")
      (node (ref "R404") (pin "1") (pinfunction "1_1") (pintype "passive"))
      (node (ref "U400") (pin "2") (pinfunction "PWM_2") (pintype "input"))
    )
    (net (code "47") (name "Net-(U400-REF)") (class "Default")
      (node (ref "C406") (pin "1") (pinfunction "1_1") (pintype "passive"))
      (node (ref "R405") (pin "2") (pinfunction "2_2") (pintype "passive"))
      (node (ref "R406") (pin "1") (pinfunction "1_1") (pintype "passive"))
      (node (ref "U400") (pin "11") (pinfunction "REF_11") (pintype "passive"))
    )
    (net (code "48") (name "Net-(U400-SENSEA)") (class "Default")
      (node (ref "R410") (pin "1") (pinfunction "1_1") (pintype "passive"))
      (node (ref "R411") (pin "1") (pinfunction "1_1") (pintype "passive"))
      (node (ref "R412") (pin "1") (pinfunction "1_1") (pintype "passive"))
      (node (ref "U400") (pin "4") (pinfunction "SENSEA_4") (pintype "output"))
      (node (ref "U400") (pin "9") (pinfunction "SENSEB_9") (pintype "output"))
    )
    (net (code "49") (name "Net-(U400-TOFF)") (class "Default")
      (node (ref "R407") (pin "1") (pinfunction "1_1") (pintype "passive"))
      (node (ref "R408") (pin "1") (pinfunction "1_1") (pintype "passive"))
      (node (ref "U400") (pin "12") (pinfunction "TOFF_12") (pintype "passive"))
    )
    (net (code "50") (name "Net-(U401-IN+)") (class "Default")
      (node (ref "C410") (pin "1") (pinfunction "1_1") (pintype "passive"))
      (node (ref "R409") (pin "1") (pinfunction "1_1") (pintype "passive"))
      (node (ref "R410") (pin "2") (pinfunction "2_2") (pintype "passive"))
      (node (ref "U401") (pin "1") (pinfunction "IN+_1") (pintype "bidirectional"))
    )
    (net (code "51") (name "Net-(U401-IN-)") (class "Default")
      (node (ref "C411") (pin "2") (pinfunction "2_2") (pintype "passive"))
      (node (ref "R413") (pin "1") (pinfunction "1_1") (pintype "passive"))
      (node (ref "R414") (pin "2") (pinfunction "2_2") (pintype "passive"))
      (node (ref "U401") (pin "5") (pinfunction "IN-_5") (pintype "bidirectional"))
    )
    (net (code "52") (name "OUT1") (class "Default")
      (node (ref "CON502") (pin "10") (pinfunction "5_10") (pintype "bidirectional"))
      (node (ref "CON502") (pin "11") (pinfunction "5_11") (pintype "bidirectional"))
      (node (ref "U400") (pin "10") (pinfunction "OUTB1_10") (pintype "output"))
      (node (ref "U400") (pin "3") (pinfunction "OUTA1_3") (pintype "output"))
    )
    (net (code "53") (name "OUT2") (class "Default")
      (node (ref "CON502") (pin "8") (pinfunction "4_8") (pintype "bidirectional"))
      (node (ref "CON502") (pin "9") (pinfunction "4_9") (pintype "bidirectional"))
      (node (ref "U400") (pin "5") (pinfunction "OUTA2_5") (pintype "output"))
      (node (ref "U400") (pin "8") (pinfunction "OUTB2_8") (pintype "output"))
    )
    (net (code "54") (name "SPI1_CS") (class "Default")
      (node (ref "U100") (pin "14") (pinfunction "PA4_14") (pintype "bidirectional"))
      (node (ref "U302") (pin "1") (pinfunction "CSN_1") (pintype "input"))
    )
    (net (code "55") (name "SPI1_MISO") (class "Default")
      (node (ref "U100") (pin "16") (pinfunction "PA6_16") (pintype "bidirectional"))
      (node (ref "U302") (pin "3") (pinfunction "MISO_3") (pintype "output"))
    )
    (net (code "56") (name "SPI1_SCK") (class "Default")
      (node (ref "U100") (pin "15") (pinfunction "PA5_15") (pintype "bidirectional"))
      (node (ref "U302") (pin "2") (pinfunction "SCLK_2") (pintype "input"))
    )
    (net (code "57") (name "SWCLK") (class "Default")
      (node (ref "C501") (pin "SWCLK") (pinfunction "9_SWCLK") (pintype "bidirectional"))
      (node (ref "U100") (pin "37") (pinfunction "PA14_37") (pintype "bidirectional"))
    )
    (net (code "58") (name "SWDIO") (class "Default")
      (node (ref "C501") (pin "SWDIO") (pinfunction "8_SWDIO") (pintype "bidirectional"))
      (node (ref "U100") (pin "34") (pinfunction "PA13_34") (pintype "bidirectional"))
    )
    (net (code "59") (name "UART_RX") (class "Default")
      (node (ref "C501") (pin "UART_RX") (pinfunction "5_UART_RX") (pintype "bidirectional"))
      (node (ref "U100") (pin "13") (pinfunction "PA3_13") (pintype "bidirectional"))
    )
    (net (code "60") (name "UART_TX") (class "Default")
      (node (ref "C501") (pin "UART_TX") (pinfunction "6_UART_TX") (pintype "bidirectional"))
      (node (ref "U100") (pin "12") (pinfunction "PA2_12") (pintype "bidirectional"))
    )
    (net (code "61") (name "VBUS") (class "Default")
      (node (ref "C201") (pin "1") (pinfunction "1_1") (pintype "passive"))
      (node (ref "C202") (pin "1") (pinfunction "1_1") (pintype "passive"))
      (node (ref "C203") (pin "1") (pinfunction "1_1") (pintype "passive"))
      (node (ref "C301") (pin "1") (pinfunction "1_1") (pintype "passive"))
      (node (ref "C302") (pin "1") (pinfunction "1_1") (pintype "passive"))
      (node (ref "C303") (pin "1") (pinfunction "1_1") (pintype "passive"))
      (node (ref "C401") (pin "1") (pinfunction "1_1") (pintype "passive"))
      (node (ref "C402") (pin "1") (pinfunction "1_1") (pintype "passive"))
      (node (ref "C403") (pin "1") (pinfunction "1_1") (pintype "passive"))
      (node (ref "C501") (pin "VBUS") (pinfunction "1_VBUS") (pintype "bidirectional"))
      (node (ref "CON502") (pin "1") (pinfunction "1_1") (pintype "bidirectional"))
      (node (ref "CON502") (pin "2") (pinfunction "1_2") (pintype "bidirectional"))
      (node (ref "CON502") (pin "3") (pinfunction "1_3") (pintype "bidirectional"))
      (node (ref "R201") (pin "2") (pinfunction "2_2") (pintype "passive"))
      (node (ref "U200") (pin "12-13") (pinfunction "VIN_12-13") (pintype "power_in"))
      (node (ref "U300") (pin "6") (pinfunction "VS_6") (pintype "power_in"))
      (node (ref "U400") (pin "6") (pinfunction "VS_6") (pintype "power_in"))
    )
    (net (code "62") (name "unconnected-(U100-PA7-Pad17)") (class "Default")
      (node (ref "U100") (pin "17") (pinfunction "PA7_17") (pintype "bidirectional"))
    )
    (net (code "63") (name "unconnected-(U100-PB0-Pad18)") (class "Default")
      (node (ref "U100") (pin "18") (pinfunction "PB0_18") (pintype "bidirectional"))
    )
    (net (code "64") (name "unconnected-(U100-PB10-Pad21)") (class "Default")
      (node (ref "U100") (pin "21") (pinfunction "PB10_21") (pintype "bidirectional"))
    )
    (net (code "65") (name "unconnected-(U100-PB11-Pad22)") (class "Default")
      (node (ref "U100") (pin "22") (pinfunction "PB11_22") (pintype "bidirectional"))
    )
    (net (code "66") (name "unconnected-(U100-PC13-Pad2)") (class "Default")
      (node (ref "U100") (pin "2") (pinfunction "PC13_2") (pintype "bidirectional"))
    )
    (net (code "67") (name "unconnected-(U100-PC14-OSC32_IN-Pad3)") (class "Default")
      (node (ref "U100") (pin "3") (pinfunction "PC14-OSC32_IN_3") (pintype "bidirectional"))
    )
    (net (code "68") (name "unconnected-(U100-PC15-OSC32_OUT-Pad4)") (class "Default")
      (node (ref "U100") (pin "4") (pinfunction "PC15-OSC32_OUT_4") (pintype "bidirectional"))
    )
    (net (code "69") (name "unconnected-(U200-FB2-Pad6)") (class "Default")
      (node (ref "U200") (pin "6") (pinfunction "FB2_6") (pintype "passive"))
    )
    (net (code "70") (name "unconnected-(U200-PG-Pad2)") (class "Default")
      (node (ref "U200") (pin "2") (pinfunction "PG_2") (pintype "open_collector"))
    )
    (net (code "71") (name "unconnected-(U302-A-Pad7)") (class "Default")
      (node (ref "U302") (pin "7") (pinfunction "A_7") (pintype "output"))
    )
    (net (code "72") (name "unconnected-(U302-B-Pad6)") (class "Default")
      (node (ref "U302") (pin "6") (pinfunction "B_6") (pintype "output"))
    )
    (net (code "73") (name "unconnected-(U302-I{slash}PWM-Pad14)") (class "Default")
      (node (ref "U302") (pin "14") (pinfunction "I/PWM_14") (pintype "output"))
    )
    (net (code "74") (name "unconnected-(U302-U-Pad10)") (class "Default")
      (node (ref "U302") (pin "10") (pinfunction "U_10") (pintype "output"))
    )
    (net (code "75") (name "unconnected-(U302-V-Pad9)") (class "Default")
      (node (ref "U302") (pin "9") (pinfunction "V_9") (pintype "output"))
    )
    (net (code "76") (name "unconnected-(U302-W{slash}PWM-Pad8)") (class "Default")
      (node (ref "U302") (pin "8") (pinfunction "W/PWM_8") (pintype "output"))
    )
  )
)
